# 05-GPS_IMU_SENSORS.net
KiCad netlist of a schematic drawn in Altium Designer
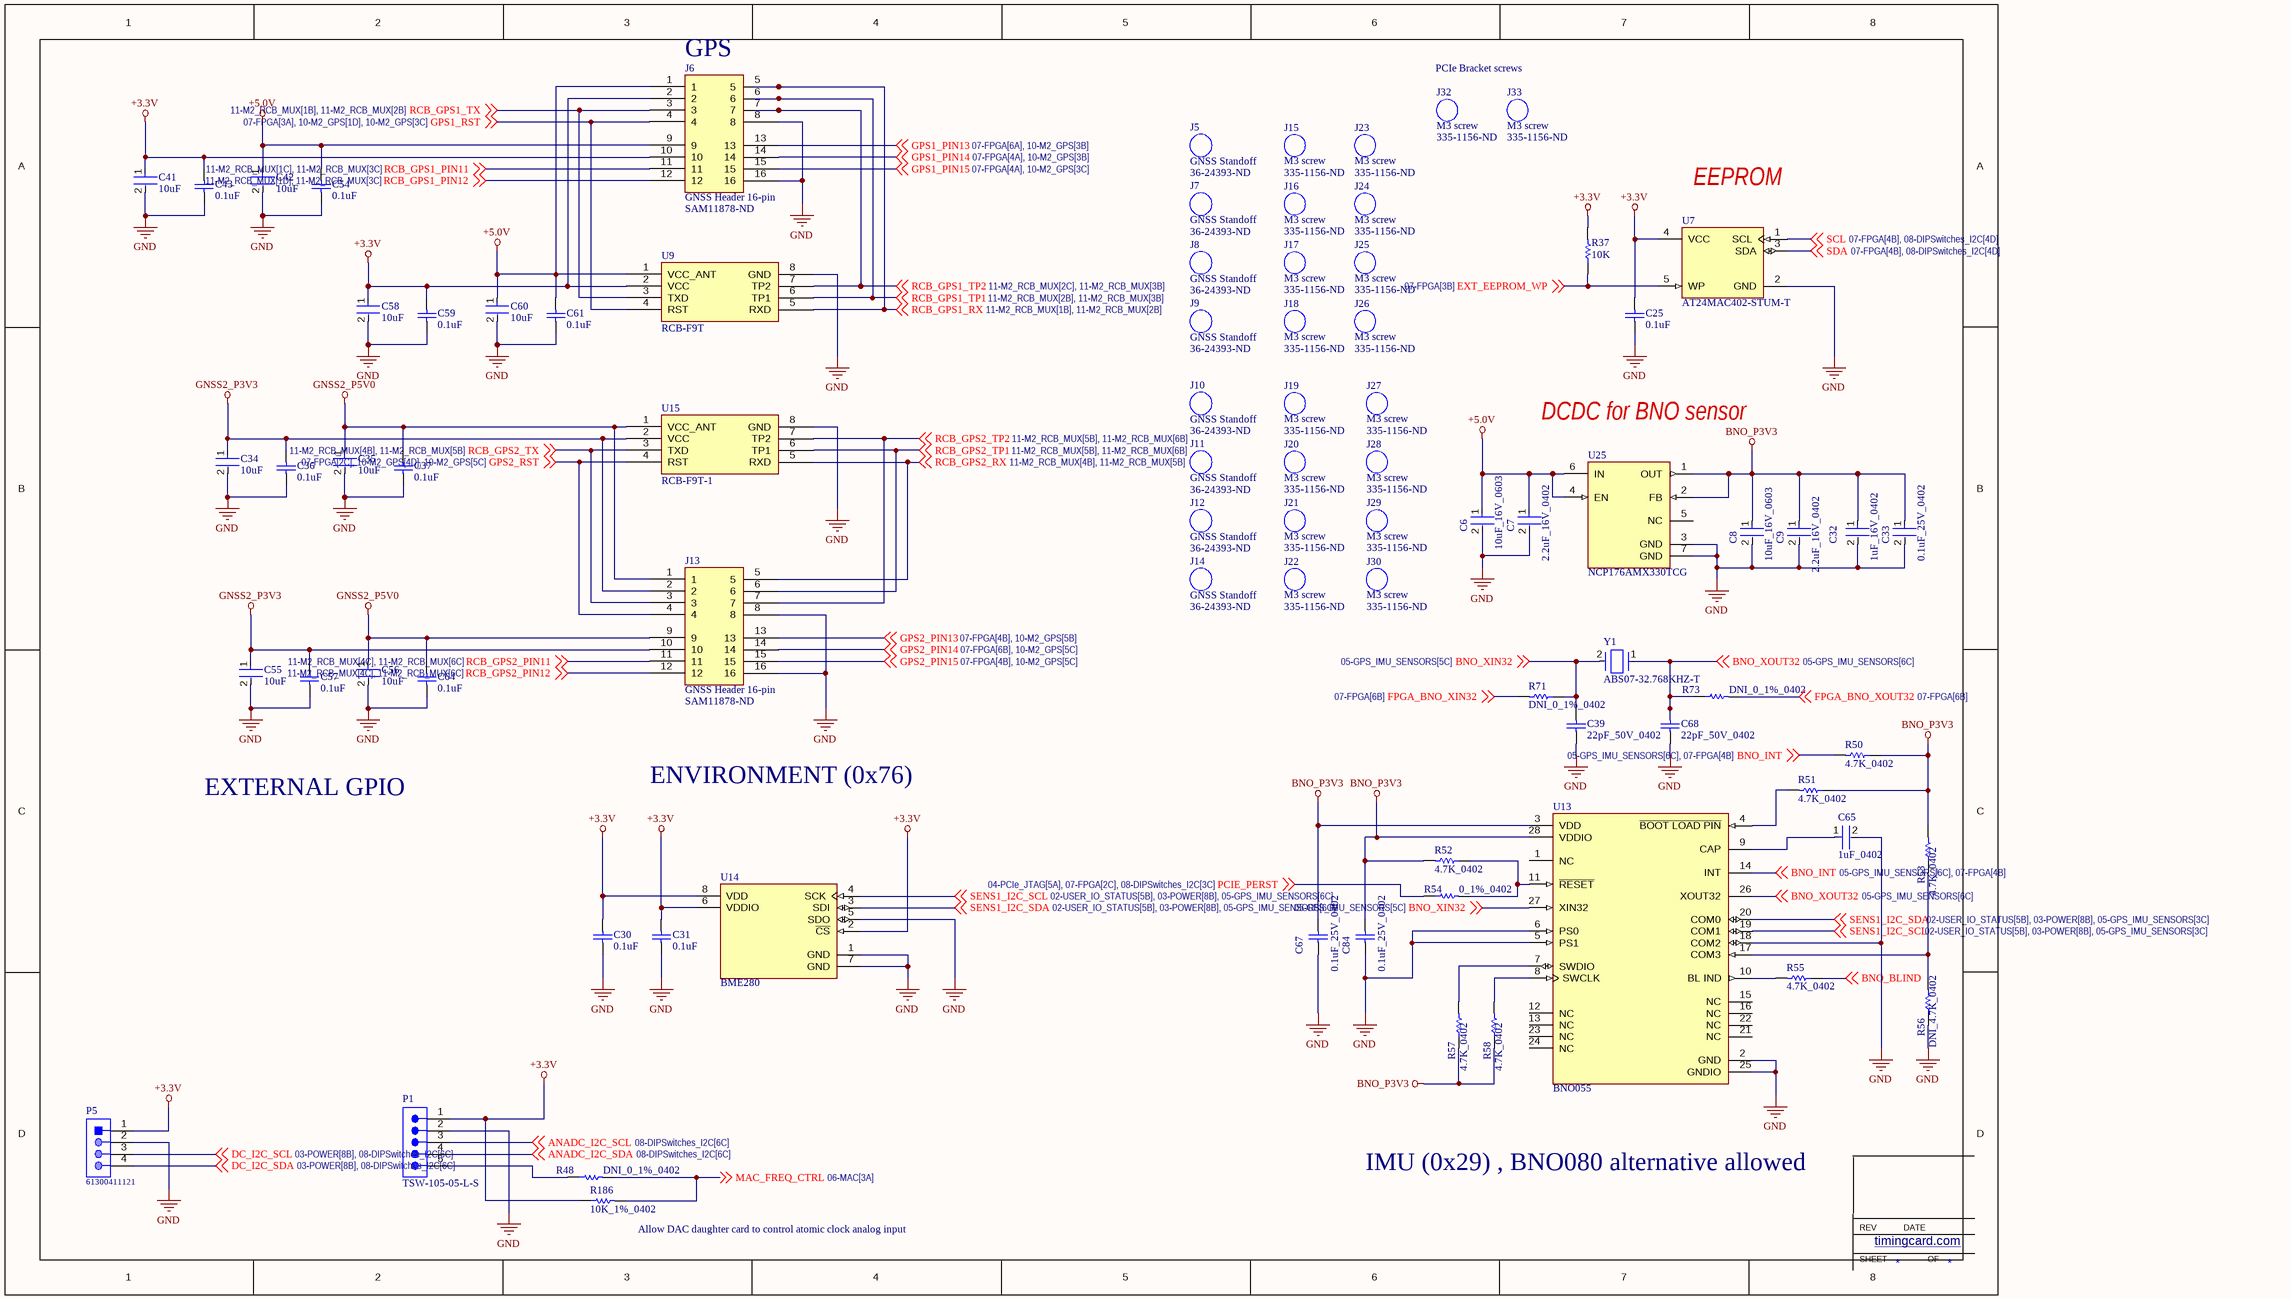
[diagram p0: 05-GPS_IMU_SENSORS.SchDoc]

(export (version "E")
  (design (tool "Eeschema 10.0.6"))
  (components
    (comp (ref "C6")
      (value "10uF_16V_0603")
      (footprint "FP-0603-L_1_6_0_2-W_0_8_0-MFG")
      (description "Multilayer Ceramic Capacitor 10uF 16V X5R 20% SMD 0603 T/R")
      (fields (field (name "TOLERANCE") "20%"))
      (libsource (lib "Altium Content Vault") (part "b4654b650e69147ec39a6b967a45e02"))
    )
    (comp (ref "C7")
      (value "2.2uF_16V_0402")
      (footprint "FP-C1005-050-0_05-IPC_A")
      (description "Multilayer Ceramic Capacitors 2.2μF ±10% 16V X5R SMD 0402")
      (fields (field (name "TOLERANCE") "10%"))
      (libsource (lib "Altium Content Vault") (part "b4654b650e69147ec39a6b967a45e02"))
    )
    (comp (ref "C8")
      (value "10uF_16V_0603")
      (footprint "FP-0603-L_1_6_0_2-W_0_8_0-MFG")
      (description "Multilayer Ceramic Capacitor 10uF 16V X5R 20% SMD 0603 T/R")
      (fields (field (name "TOLERANCE") "20%"))
      (libsource (lib "Altium Content Vault") (part "b4654b650e69147ec39a6b967a45e02"))
    )
    (comp (ref "C9")
      (value "2.2uF_16V_0402")
      (footprint "FP-C1005-050-0_05-IPC_A")
      (description "Multilayer Ceramic Capacitors 2.2μF ±10% 16V X5R SMD 0402")
      (fields (field (name "TOLERANCE") "10%"))
      (libsource (lib "Altium Content Vault") (part "b4654b650e69147ec39a6b967a45e02"))
    )
    (comp (ref "C25")
      (value "0.1uF")
      (footprint "CAPC1608X87X45ML20T05")
      (description "C0603X104K5RACAUTO")
      (fields (field (name "MANUFACTURER") "Kemet"))
      (libsource (lib "Altium Content Vault") (part "CAP"))
    )
    (comp (ref "C30")
      (value "0.1uF")
      (footprint "CAPC1608X87X45ML20T05")
      (description "C0603X104K5RACAUTO")
      (fields (field (name "MANUFACTURER") "Kemet"))
      (libsource (lib "Altium Content Vault") (part "CAP"))
    )
    (comp (ref "C31")
      (value "0.1uF")
      (footprint "CAPC1608X87X45ML20T05")
      (description "C0603X104K5RACAUTO")
      (fields (field (name "MANUFACTURER") "Kemet"))
      (libsource (lib "Altium Content Vault") (part "CAP"))
    )
    (comp (ref "C32")
      (value "1uF_16V_0402")
      (footprint "FP-0402-L_1_0_0_05-W_0_5-IPC_A")
      (description "None")
      (fields (field (name "TOLERANCE") "10%"))
      (libsource (lib "Altium Content Vault") (part "b4654b650e69147ec39a6b967a45e02"))
    )
    (comp (ref "C33")
      (value "0.1uF_25V_0402")
      (footprint "FP-0402-L_1_0_1-W_0_5_0_1-IPC_C")
      (description "General Purpose Ceramic Capacitor, 0402, 100nF, 10%, X7R, 15%, 25V")
      (fields (field (name "VOLTAGE") "25V") (field (name "TOLERANCE") "10%"))
      (libsource (lib "Altium Content Vault") (part "b4654b650e69147ec39a6b967a45e02"))
    )
    (comp (ref "C34")
      (value "10uF")
      (footprint "FP-MK212BG-MFG")
      (description "None")
      (fields (field (name "TOLERANCE") "10%") (field (name "VOLTAGE") "16V"))
      (libsource (lib "Altium Content Vault") (part "b4654b650e69147ec39a6b967a45e02"))
    )
    (comp (ref "C35")
      (value "10uF")
      (footprint "FP-MK212BG-MFG")
      (description "None")
      (fields (field (name "TOLERANCE") "10%") (field (name "VOLTAGE") "16V"))
      (libsource (lib "Altium Content Vault") (part "b4654b650e69147ec39a6b967a45e02"))
    )
    (comp (ref "C36")
      (value "0.1uF")
      (footprint "CAPC1608X87X45ML20T05")
      (description "C0603X104K5RACAUTO")
      (fields (field (name "MANUFACTURER") "Kemet"))
      (libsource (lib "Altium Content Vault") (part "CAP"))
    )
    (comp (ref "C37")
      (value "0.1uF")
      (footprint "CAPC1608X87X45ML20T05")
      (description "C0603X104K5RACAUTO")
      (fields (field (name "MANUFACTURER") "Kemet"))
      (libsource (lib "Altium Content Vault") (part "CAP"))
    )
    (comp (ref "C39")
      (value "22pF_50V_0402")
      (footprint "CAPC1005X55X25ML05T05")
      (description "Chip Capacitor, 22 pF, +/- 5%, 50 V, -55 to 125 degC, 0402 (1005 Metric), RoHS, Tape and Reel")
      (fields (field (name "MANUFACTURER") "Yageo") (field (name "TOLERANCE") "5%"))
      (libsource (lib "Altium Content Vault") (part "CAP-NP-2"))
    )
    (comp (ref "C41")
      (value "10uF")
      (footprint "FP-MK212BG-MFG")
      (description "None")
      (fields (field (name "TOLERANCE") "10%") (field (name "VOLTAGE") "16V"))
      (libsource (lib "Altium Content Vault") (part "b4654b650e69147ec39a6b967a45e02"))
    )
    (comp (ref "C42")
      (value "10uF")
      (footprint "FP-MK212BG-MFG")
      (description "None")
      (fields (field (name "TOLERANCE") "10%") (field (name "VOLTAGE") "16V"))
      (libsource (lib "Altium Content Vault") (part "b4654b650e69147ec39a6b967a45e02"))
    )
    (comp (ref "C43")
      (value "0.1uF")
      (footprint "CAPC1608X87X45ML20T05")
      (description "C0603X104K5RACAUTO")
      (fields (field (name "MANUFACTURER") "Kemet"))
      (libsource (lib "Altium Content Vault") (part "CAP"))
    )
    (comp (ref "C54")
      (value "0.1uF")
      (footprint "CAPC1608X87X45ML20T05")
      (description "C0603X104K5RACAUTO")
      (fields (field (name "MANUFACTURER") "Kemet"))
      (libsource (lib "Altium Content Vault") (part "CAP"))
    )
    (comp (ref "C55")
      (value "10uF")
      (footprint "FP-MK212BG-MFG")
      (description "None")
      (fields (field (name "TOLERANCE") "10%") (field (name "VOLTAGE") "16V"))
      (libsource (lib "Altium Content Vault") (part "b4654b650e69147ec39a6b967a45e02"))
    )
    (comp (ref "C56")
      (value "10uF")
      (footprint "FP-MK212BG-MFG")
      (description "None")
      (fields (field (name "TOLERANCE") "10%") (field (name "VOLTAGE") "16V"))
      (libsource (lib "Altium Content Vault") (part "b4654b650e69147ec39a6b967a45e02"))
    )
    (comp (ref "C57")
      (value "0.1uF")
      (footprint "CAPC1608X87X45ML20T05")
      (description "C0603X104K5RACAUTO")
      (fields (field (name "MANUFACTURER") "Kemet"))
      (libsource (lib "Altium Content Vault") (part "CAP"))
    )
    (comp (ref "C58")
      (value "10uF")
      (footprint "FP-MK212BG-MFG")
      (description "None")
      (fields (field (name "TOLERANCE") "10%") (field (name "VOLTAGE") "16V"))
      (libsource (lib "Altium Content Vault") (part "b4654b650e69147ec39a6b967a45e02"))
    )
    (comp (ref "C59")
      (value "0.1uF")
      (footprint "CAPC1608X87X45ML20T05")
      (description "C0603X104K5RACAUTO")
      (fields (field (name "MANUFACTURER") "Kemet"))
      (libsource (lib "Altium Content Vault") (part "CAP"))
    )
    (comp (ref "C60")
      (value "10uF")
      (footprint "FP-MK212BG-MFG")
      (description "None")
      (fields (field (name "TOLERANCE") "10%") (field (name "VOLTAGE") "16V"))
      (libsource (lib "Altium Content Vault") (part "b4654b650e69147ec39a6b967a45e02"))
    )
    (comp (ref "C61")
      (value "0.1uF")
      (footprint "CAPC1608X87X45ML20T05")
      (description "C0603X104K5RACAUTO")
      (fields (field (name "MANUFACTURER") "Kemet"))
      (libsource (lib "Altium Content Vault") (part "CAP"))
    )
    (comp (ref "C64")
      (value "0.1uF")
      (footprint "CAPC1608X87X45ML20T05")
      (description "C0603X104K5RACAUTO")
      (fields (field (name "MANUFACTURER") "Kemet"))
      (libsource (lib "Altium Content Vault") (part "CAP"))
    )
    (comp (ref "C65")
      (value "1uF_0402")
      (footprint "FP-0402-L_1_0_0_05-W_0_5-IPC_C")
      (description "None")
      (fields (field (name "TOLERANCE") "20%") (field (name "VOLTAGE") "16V"))
      (libsource (lib "Altium Content Vault") (part "b4654b650e69147ec39a6b967a45e02"))
    )
    (comp (ref "C67")
      (value "0.1uF_25V_0402")
      (footprint "CAPC1005X56X25NL10T15")
      (fields
        (field (name "PART NUMBER") "04023D104KAT2A")
        (field (name "MANUFACTURER") "AVX Interconnect / Elco")
      )
      (libsource (lib "Altium Content Vault") (part "CAP"))
    )
    (comp (ref "C68")
      (value "22pF_50V_0402")
      (footprint "CAPC1005X55X25ML05T05")
      (description "Chip Capacitor, 22 pF, +/- 5%, 50 V, -55 to 125 degC, 0402 (1005 Metric), RoHS, Tape and Reel")
      (fields (field (name "MANUFACTURER") "Yageo") (field (name "TOLERANCE") "5%"))
      (libsource (lib "Altium Content Vault") (part "CAP-NP-2"))
    )
    (comp (ref "C84")
      (value "0.1uF_25V_0402")
      (footprint "CAPC1005X56X25NL10T15")
      (fields
        (field (name "PART NUMBER") "04023D104KAT2A")
        (field (name "MANUFACTURER") "AVX Interconnect / Elco")
      )
      (libsource (lib "Altium Content Vault") (part "CAP"))
    )
    (comp (ref "J5")
      (value "GNSS Standoff")
      (fields (field (name "SUPPLIER PART NUMBER 1") "36-24393-ND"))
      (libsource (lib "FPGA_CONN") (part "GNSS Standoff"))
    )
    (comp (ref "J6")
      (value "GNSS Header 16-pin")
      (footprint "GNSS Header 16-pin")
      (fields (field (name "SUPPLIER PART NUMBER 1") "SAM11878-ND"))
      (libsource (lib "FPGA_CONN") (part "GNSS Header 16-pin"))
    )
    (comp (ref "J7")
      (value "GNSS Standoff")
      (fields (field (name "SUPPLIER PART NUMBER 1") "36-24393-ND"))
      (libsource (lib "FPGA_CONN") (part "GNSS Standoff"))
    )
    (comp (ref "J8")
      (value "GNSS Standoff")
      (fields (field (name "SUPPLIER PART NUMBER 1") "36-24393-ND"))
      (libsource (lib "FPGA_CONN") (part "GNSS Standoff"))
    )
    (comp (ref "J9")
      (value "GNSS Standoff")
      (fields (field (name "SUPPLIER PART NUMBER 1") "36-24393-ND"))
      (libsource (lib "FPGA_CONN") (part "GNSS Standoff"))
    )
    (comp (ref "J10")
      (value "GNSS Standoff")
      (fields (field (name "SUPPLIER PART NUMBER 1") "36-24393-ND"))
      (libsource (lib "FPGA_CONN") (part "GNSS Standoff"))
    )
    (comp (ref "J11")
      (value "GNSS Standoff")
      (fields (field (name "SUPPLIER PART NUMBER 1") "36-24393-ND"))
      (libsource (lib "FPGA_CONN") (part "GNSS Standoff"))
    )
    (comp (ref "J12")
      (value "GNSS Standoff")
      (fields (field (name "SUPPLIER PART NUMBER 1") "36-24393-ND"))
      (libsource (lib "FPGA_CONN") (part "GNSS Standoff"))
    )
    (comp (ref "J13")
      (value "GNSS Header 16-pin")
      (footprint "GNSS Header 16-pin")
      (fields (field (name "SUPPLIER PART NUMBER 1") "SAM11878-ND"))
      (libsource (lib "FPGA_CONN") (part "GNSS Header 16-pin"))
    )
    (comp (ref "J14")
      (value "GNSS Standoff")
      (fields (field (name "SUPPLIER PART NUMBER 1") "36-24393-ND"))
      (libsource (lib "FPGA_CONN") (part "GNSS Standoff"))
    )
    (comp (ref "J15")
      (value "M3 screw")
      (fields (field (name "SUPPLIER PART NUMBER 1") "335-1156-ND"))
      (libsource (lib "FPGA_CONN") (part "M3 screw"))
    )
    (comp (ref "J16")
      (value "M3 screw")
      (fields (field (name "SUPPLIER PART NUMBER 1") "335-1156-ND"))
      (libsource (lib "FPGA_CONN") (part "M3 screw"))
    )
    (comp (ref "J17")
      (value "M3 screw")
      (fields (field (name "SUPPLIER PART NUMBER 1") "335-1156-ND"))
      (libsource (lib "FPGA_CONN") (part "M3 screw"))
    )
    (comp (ref "J18")
      (value "M3 screw")
      (fields (field (name "SUPPLIER PART NUMBER 1") "335-1156-ND"))
      (libsource (lib "FPGA_CONN") (part "M3 screw"))
    )
    (comp (ref "J19")
      (value "M3 screw")
      (fields (field (name "SUPPLIER PART NUMBER 1") "335-1156-ND"))
      (libsource (lib "FPGA_CONN") (part "M3 screw"))
    )
    (comp (ref "J20")
      (value "M3 screw")
      (fields (field (name "SUPPLIER PART NUMBER 1") "335-1156-ND"))
      (libsource (lib "FPGA_CONN") (part "M3 screw"))
    )
    (comp (ref "J21")
      (value "M3 screw")
      (fields (field (name "SUPPLIER PART NUMBER 1") "335-1156-ND"))
      (libsource (lib "FPGA_CONN") (part "M3 screw"))
    )
    (comp (ref "J22")
      (value "M3 screw")
      (fields (field (name "SUPPLIER PART NUMBER 1") "335-1156-ND"))
      (libsource (lib "FPGA_CONN") (part "M3 screw"))
    )
    (comp (ref "J23")
      (value "M3 screw")
      (fields (field (name "SUPPLIER PART NUMBER 1") "335-1156-ND"))
      (libsource (lib "FPGA_CONN") (part "M3 screw"))
    )
    (comp (ref "J24")
      (value "M3 screw")
      (fields (field (name "SUPPLIER PART NUMBER 1") "335-1156-ND"))
      (libsource (lib "FPGA_CONN") (part "M3 screw"))
    )
    (comp (ref "J25")
      (value "M3 screw")
      (fields (field (name "SUPPLIER PART NUMBER 1") "335-1156-ND"))
      (libsource (lib "FPGA_CONN") (part "M3 screw"))
    )
    (comp (ref "J26")
      (value "M3 screw")
      (fields (field (name "SUPPLIER PART NUMBER 1") "335-1156-ND"))
      (libsource (lib "FPGA_CONN") (part "M3 screw"))
    )
    (comp (ref "J27")
      (value "M3 screw")
      (fields (field (name "SUPPLIER PART NUMBER 1") "335-1156-ND"))
      (libsource (lib "FPGA_CONN") (part "M3 screw"))
    )
    (comp (ref "J28")
      (value "M3 screw")
      (fields (field (name "SUPPLIER PART NUMBER 1") "335-1156-ND"))
      (libsource (lib "FPGA_CONN") (part "M3 screw"))
    )
    (comp (ref "J29")
      (value "M3 screw")
      (fields (field (name "SUPPLIER PART NUMBER 1") "335-1156-ND"))
      (libsource (lib "FPGA_CONN") (part "M3 screw"))
    )
    (comp (ref "J30")
      (value "M3 screw")
      (fields (field (name "SUPPLIER PART NUMBER 1") "335-1156-ND"))
      (libsource (lib "FPGA_CONN") (part "M3 screw"))
    )
    (comp (ref "J32")
      (value "M3 screw")
      (fields (field (name "SUPPLIER PART NUMBER 1") "335-1156-ND"))
      (libsource (lib "FPGA_CONN") (part "M3 screw"))
    )
    (comp (ref "J33")
      (value "M3 screw")
      (fields (field (name "SUPPLIER PART NUMBER 1") "335-1156-ND"))
      (libsource (lib "FPGA_CONN") (part "M3 screw"))
    )
    (comp (ref "P1")
      (value "TSW-105-05-L-S")
      (footprint "SMTC-TSW-105-05-X-S")
      (description "0.025\" SQ Post Header, Through-hole, Vertical, -55 to 125 degC, 2.54 mm Pitch, 5-Pin, Male, RoHS")
      (fields (field (name "MANUFACTURER") "Samtec"))
      (libsource (lib "Altium Content Vault") (part "SMTC-TSW-105-05-X-S"))
    )
    (comp (ref "P5")
      (value "61300411121")
      (footprint "61300411121")
      (description "THT Vertical Pin Header WR-PHD, Pitch 2.54 mm, Single Row, 4 pins")
      (fields (field (name "MANUFACTURER") "Wurth Elektronik") (field (name "PUBLISHER") "WurthElektronik"))
      (libsource (lib "Altium Content Vault") (part "WE-CN-1P-M-R4"))
    )
    (comp (ref "R37")
      (value "10K")
      (footprint "RESC1608X55X30LL15T20")
      (fields (field (name "TOLERANCE") "±1%") (field (name "MANUFACTURER") "Stackpole-Electronics-Inc."))
      (libsource (lib "Altium Content Vault") (part "RES-2"))
    )
    (comp (ref "R48")
      (value "DNI_0_1%_0402")
      (footprint "RESC1005X40X25LL05T05")
      (description "Chip Resistor, 0 Ohm, 0.1 W, -55 to 155 degC, 0402 (1005 Metric), RoHS, Tape and Reel")
      (fields (field (name "MANUFACTURER") "Panasonic") (field (name "TOLERANCE") "5%"))
      (libsource (lib "Altium Content Vault") (part "RES-2"))
    )
    (comp (ref "R50")
      (value "4.7K_0402")
      (footprint "RESC1005X40X25LL05T05")
      (description "Chip Resistor, 4.7 KOhm, +/- 1%, 0.1 W, -55 to 155 degC, 0402 (1005 Metric), RoHS, Tape and Reel")
      (fields (field (name "TOLERANCE") "1%") (field (name "PARTNUMBER") "ERJ-2RKF4701X"))
      (libsource (lib "Altium Content Vault") (part "RES-2"))
    )
    (comp (ref "R51")
      (value "4.7K_0402")
      (footprint "RESC1005X40X25LL05T05")
      (description "Chip Resistor, 4.7 KOhm, +/- 1%, 0.1 W, -55 to 155 degC, 0402 (1005 Metric), RoHS, Tape and Reel")
      (fields (field (name "TOLERANCE") "1%") (field (name "PARTNUMBER") "ERJ-2RKF4701X"))
      (libsource (lib "Altium Content Vault") (part "RES-2"))
    )
    (comp (ref "R52")
      (value "4.7K_0402")
      (footprint "RESC1005X40X25LL05T05")
      (description "Chip Resistor, 4.7 KOhm, +/- 1%, 0.1 W, -55 to 155 degC, 0402 (1005 Metric), RoHS, Tape and Reel")
      (fields (field (name "TOLERANCE") "1%") (field (name "PARTNUMBER") "ERJ-2RKF4701X"))
      (libsource (lib "Altium Content Vault") (part "RES-2"))
    )
    (comp (ref "R53")
      (value "4.7K_0402")
      (footprint "RESC1005X40X25LL05T05")
      (description "Chip Resistor, 4.7 KOhm, +/- 1%, 0.1 W, -55 to 155 degC, 0402 (1005 Metric), RoHS, Tape and Reel")
      (fields (field (name "TOLERANCE") "1%") (field (name "PARTNUMBER") "ERJ-2RKF4701X"))
      (libsource (lib "Altium Content Vault") (part "RES-2"))
    )
    (comp (ref "R54")
      (value "0_1%_0402")
      (footprint "RESC1005X40X25LL05T05")
      (description "Chip Resistor, 0 Ohm, 0.1 W, -55 to 155 degC, 0402 (1005 Metric), RoHS, Tape and Reel")
      (fields (field (name "MANUFACTURER") "Panasonic") (field (name "TOLERANCE") "5%"))
      (libsource (lib "Altium Content Vault") (part "RES-2"))
    )
    (comp (ref "R55")
      (value "4.7K_0402")
      (footprint "RESC1005X40X25LL05T05")
      (description "Chip Resistor, 4.7 KOhm, +/- 1%, 0.1 W, -55 to 155 degC, 0402 (1005 Metric), RoHS, Tape and Reel")
      (fields (field (name "TOLERANCE") "1%") (field (name "PARTNUMBER") "ERJ-2RKF4701X"))
      (libsource (lib "Altium Content Vault") (part "RES-2"))
    )
    (comp (ref "R56")
      (value "DNI_4.7K_0402")
      (footprint "RESC1005X40X25LL05T05")
      (description "Chip Resistor, 4.7 KOhm, +/- 1%, 0.1 W, -55 to 155 degC, 0402 (1005 Metric), RoHS, Tape and Reel")
      (fields (field (name "TOLERANCE") "1%") (field (name "PARTNUMBER") "ERJ-2RKF4701X"))
      (libsource (lib "Altium Content Vault") (part "RES-2"))
    )
    (comp (ref "R57")
      (value "4.7K_0402")
      (footprint "RESC1005X40X25LL05T05")
      (description "Chip Resistor, 4.7 KOhm, +/- 1%, 0.1 W, -55 to 155 degC, 0402 (1005 Metric), RoHS, Tape and Reel")
      (fields (field (name "TOLERANCE") "1%") (field (name "PARTNUMBER") "ERJ-2RKF4701X"))
      (libsource (lib "Altium Content Vault") (part "RES-2"))
    )
    (comp (ref "R58")
      (value "4.7K_0402")
      (footprint "RESC1005X40X25LL05T05")
      (description "Chip Resistor, 4.7 KOhm, +/- 1%, 0.1 W, -55 to 155 degC, 0402 (1005 Metric), RoHS, Tape and Reel")
      (fields (field (name "TOLERANCE") "1%") (field (name "PARTNUMBER") "ERJ-2RKF4701X"))
      (libsource (lib "Altium Content Vault") (part "RES-2"))
    )
    (comp (ref "R71")
      (value "DNI_0_1%_0402")
      (footprint "RESC1005X40X25LL05T05")
      (description "Chip Resistor, 0 Ohm, 0.1 W, -55 to 155 degC, 0402 (1005 Metric), RoHS, Tape and Reel")
      (fields (field (name "MANUFACTURER") "Panasonic") (field (name "TOLERANCE") "5%"))
      (libsource (lib "Altium Content Vault") (part "RES-2"))
    )
    (comp (ref "R73")
      (value "DNI_0_1%_0402")
      (footprint "RESC1005X40X25LL05T05")
      (description "Chip Resistor, 0 Ohm, 0.1 W, -55 to 155 degC, 0402 (1005 Metric), RoHS, Tape and Reel")
      (fields (field (name "MANUFACTURER") "Panasonic") (field (name "TOLERANCE") "5%"))
      (libsource (lib "Altium Content Vault") (part "RES-2"))
    )
    (comp (ref "R186")
      (value "10K_1%_0402")
      (footprint "RESC1005X40X25LL05T10")
      (fields (field (name "PART NUMBER") "RC0402FR-0710KL") (field (name "MANUFACTURER") "Yageo / Phycomp"))
      (libsource (lib "Altium Content Vault") (part "RES"))
    )
    (comp (ref "U7")
      (value "AT24MAC402-STUM-T")
      (footprint "FP-5TS1-IPC_C")
      (description "IC EEPROM 2K I2C 1MHZ SOT23-5")
      (fields
        (field (name "MANUFACTURER") "Microchip")
        (field (name "OCTOPART") "https://octopart.com/at24mac402-stum-t-microchip-77758112")
      )
      (libsource (lib "Altium Content Vault") (part "93fe34f5f049140596bab6421a6454b"))
    )
    (comp (ref "U9")
      (value "RCB-F9T")
      (footprint "GNSS")
      (description "MOD, GPS")
      (fields (field (name "VELENTIUM PART NUM") "<V PART NUM>"))
      (libsource (lib "Modules") (part "RCB-F9T"))
    )
    (comp (ref "U13")
      (value "BNO055")
      (footprint "FP-BNO055-MFG")
      (description "IMU ACCEL/GYRO/MAG I2C 28LGA")
      (libsource (lib "Altium Content Vault") (part "ba837af00a0b6167256f888b31462b1"))
    )
    (comp (ref "U14")
      (value "BME280")
      (footprint "FP-BME280-MFG")
      (description "SENSOR PRESSURE HUMIDITY TEMP")
      (libsource (lib "Altium Content Vault") (part "d58e2f6669bc67e6a2bc6a28610ca79"))
    )
    (comp (ref "U15")
      (value "RCB-F9T-1")
      (footprint "GNSS")
      (description "MOD, GPS")
      (fields (field (name "VELENTIUM PART NUM") "<V PART NUM>"))
      (libsource (lib "Modules") (part "RCB-F9T"))
    )
    (comp (ref "U25")
      (value "NCP176AMX330TCG")
      (footprint "FP-711AT-MFG")
      (description "IC REG LINEAR 3.3V 500MA 6XDFN")
      (fields
        (field (name "MANUFACTURER") "ON Semiconductor")
        (field (name "OCTOPART") "https://octopart.com/ncp176amx330tcg-on+semiconductor-61522616")
      )
      (libsource (lib "Altium Content Vault") (part "a38d0f79c2a9f01c07a7e52882ed186"))
    )
    (comp (ref "Y1")
      (value "ABS07-32.768KHZ-T")
      (footprint "FP-ABS07-MFG")
      (description "Crystal 32.768kHz ±20ppm (Tol) 12.5pF FUND 70kΩ 2-Pin CSMD T/R")
      (fields (field (name "TOLERANCE") "20ppm"))
      (libsource (lib "Altium Content Vault") (part "c23a69dc6c9e2f18f2079038eb95dd1"))
    )
  )
  (nets
    (net (code "1") (name "+3.3V") (class "Default")
      (node (ref "C25") (pin "2") (pinfunction "2_2") (pintype "passive"))
      (node (ref "C30") (pin "2") (pinfunction "2_2") (pintype "passive"))
      (node (ref "C31") (pin "2") (pinfunction "2_2") (pintype "passive"))
      (node (ref "C41") (pin "1") (pinfunction "1_1") (pintype "passive"))
      (node (ref "C43") (pin "2") (pinfunction "2_2") (pintype "passive"))
      (node (ref "C58") (pin "1") (pinfunction "1_1") (pintype "passive"))
      (node (ref "C59") (pin "2") (pinfunction "2_2") (pintype "passive"))
      (node (ref "J6") (pin "10") (pinfunction "10_10") (pintype "passive"))
      (node (ref "J6") (pin "2") (pinfunction "2_2") (pintype "passive"))
      (node (ref "P1") (pin "1") (pinfunction "1_1") (pintype "passive"))
      (node (ref "P5") (pin "1") (pinfunction "1_1") (pintype "passive"))
      (node (ref "R186") (pin "1") (pinfunction "1_1") (pintype "passive"))
      (node (ref "R37") (pin "2") (pinfunction "2_2") (pintype "passive"))
      (node (ref "U14") (pin "2") (pinfunction "~{CS}_2") (pintype "input"))
      (node (ref "U14") (pin "6") (pinfunction "VDDIO_6") (pintype "power_in"))
      (node (ref "U14") (pin "8") (pinfunction "VDD_8") (pintype "power_in"))
      (node (ref "U7") (pin "4") (pinfunction "VCC_4") (pintype "power_in"))
      (node (ref "U9") (pin "2") (pinfunction "VCC_2") (pintype "passive"))
    )
    (net (code "2") (name "+5.0V") (class "Default")
      (node (ref "C42") (pin "1") (pinfunction "1_1") (pintype "passive"))
      (node (ref "C54") (pin "2") (pinfunction "2_2") (pintype "passive"))
      (node (ref "C6") (pin "1") (pinfunction "1_1") (pintype "passive"))
      (node (ref "C60") (pin "1") (pinfunction "1_1") (pintype "passive"))
      (node (ref "C61") (pin "2") (pinfunction "2_2") (pintype "passive"))
      (node (ref "C7") (pin "1") (pinfunction "1_1") (pintype "passive"))
      (node (ref "J6") (pin "1") (pinfunction "1_1") (pintype "passive"))
      (node (ref "J6") (pin "9") (pinfunction "9_9") (pintype "passive"))
      (node (ref "U25") (pin "4") (pinfunction "EN_4") (pintype "input"))
      (node (ref "U25") (pin "6") (pinfunction "IN_6") (pintype "power_in"))
      (node (ref "U9") (pin "1") (pinfunction "VCC_ANT_1") (pintype "passive"))
    )
    (net (code "3") (name "ANADC_I2C_SCL") (class "Default")
      (node (ref "P1") (pin "3") (pinfunction "3_3") (pintype "passive"))
    )
    (net (code "4") (name "ANADC_I2C_SDA") (class "Default")
      (node (ref "P1") (pin "4") (pinfunction "4_4") (pintype "passive"))
    )
    (net (code "5") (name "BNO_BLIND") (class "Default")
      (node (ref "R55") (pin "1") (pinfunction "1_1") (pintype "passive"))
    )
    (net (code "6") (name "BNO_INT") (class "Default")
      (node (ref "R50") (pin "2") (pinfunction "2_2") (pintype "passive"))
      (node (ref "U13") (pin "14") (pinfunction "INT_14") (pintype "passive"))
    )
    (net (code "7") (name "BNO_P3V3") (class "Default")
      (node (ref "C32") (pin "1") (pinfunction "1_1") (pintype "passive"))
      (node (ref "C33") (pin "1") (pinfunction "1_1") (pintype "passive"))
      (node (ref "C67") (pin "2") (pinfunction "2_2") (pintype "passive"))
      (node (ref "C8") (pin "1") (pinfunction "1_1") (pintype "passive"))
      (node (ref "C84") (pin "2") (pinfunction "2_2") (pintype "passive"))
      (node (ref "C9") (pin "1") (pinfunction "1_1") (pintype "passive"))
      (node (ref "R50") (pin "1") (pinfunction "1_1") (pintype "passive"))
      (node (ref "R51") (pin "1") (pinfunction "1_1") (pintype "passive"))
      (node (ref "R52") (pin "2") (pinfunction "2_2") (pintype "passive"))
      (node (ref "R53") (pin "2") (pinfunction "2_2") (pintype "passive"))
      (node (ref "R57") (pin "1") (pinfunction "1_1") (pintype "passive"))
      (node (ref "R58") (pin "1") (pinfunction "1_1") (pintype "passive"))
      (node (ref "U13") (pin "28") (pinfunction "VDDIO_28") (pintype "power_in"))
      (node (ref "U13") (pin "3") (pinfunction "VDD_3") (pintype "power_in"))
      (node (ref "U25") (pin "1") (pinfunction "OUT_1") (pintype "output"))
      (node (ref "U25") (pin "2") (pinfunction "FB_2") (pintype "input"))
    )
    (net (code "8") (name "BNO_XIN32") (class "Default")
      (node (ref "C39") (pin "2") (pinfunction "2_2") (pintype "passive"))
      (node (ref "R71") (pin "1") (pinfunction "1_1") (pintype "passive"))
      (node (ref "U13") (pin "27") (pinfunction "XIN32_27") (pintype "input"))
      (node (ref "Y1") (pin "2") (pinfunction "2_2") (pintype "passive"))
    )
    (net (code "9") (name "BNO_XOUT32") (class "Default")
      (node (ref "C68") (pin "2") (pinfunction "2_2") (pintype "passive"))
      (node (ref "R73") (pin "1") (pinfunction "1_1") (pintype "passive"))
      (node (ref "U13") (pin "26") (pinfunction "XOUT32_26") (pintype "passive"))
      (node (ref "Y1") (pin "1") (pinfunction "1_1") (pintype "passive"))
    )
    (net (code "10") (name "DC_I2C_SCL") (class "Default")
      (node (ref "P5") (pin "3") (pinfunction "3_3") (pintype "passive"))
    )
    (net (code "11") (name "DC_I2C_SDA") (class "Default")
      (node (ref "P5") (pin "4") (pinfunction "4_4") (pintype "passive"))
    )
    (net (code "12") (name "EXT_EEPROM_WP") (class "Default")
      (node (ref "R37") (pin "1") (pinfunction "1_1") (pintype "passive"))
      (node (ref "U7") (pin "5") (pinfunction "WP_5") (pintype "input"))
    )
    (net (code "13") (name "FPGA_BNO_XIN32") (class "Default")
      (node (ref "R71") (pin "2") (pinfunction "2_2") (pintype "passive"))
    )
    (net (code "14") (name "FPGA_BNO_XOUT32") (class "Default")
      (node (ref "R73") (pin "2") (pinfunction "2_2") (pintype "passive"))
    )
    (net (code "15") (name "GND") (class "Default")
      (node (ref "C25") (pin "1") (pinfunction "1_1") (pintype "passive"))
      (node (ref "C30") (pin "1") (pinfunction "1_1") (pintype "passive"))
      (node (ref "C31") (pin "1") (pinfunction "1_1") (pintype "passive"))
      (node (ref "C32") (pin "2") (pinfunction "2_2") (pintype "passive"))
      (node (ref "C33") (pin "2") (pinfunction "2_2") (pintype "passive"))
      (node (ref "C34") (pin "2") (pinfunction "2_2") (pintype "passive"))
      (node (ref "C35") (pin "2") (pinfunction "2_2") (pintype "passive"))
      (node (ref "C36") (pin "1") (pinfunction "1_1") (pintype "passive"))
      (node (ref "C37") (pin "1") (pinfunction "1_1") (pintype "passive"))
      (node (ref "C39") (pin "1") (pinfunction "1_1") (pintype "passive"))
      (node (ref "C41") (pin "2") (pinfunction "2_2") (pintype "passive"))
      (node (ref "C42") (pin "2") (pinfunction "2_2") (pintype "passive"))
      (node (ref "C43") (pin "1") (pinfunction "1_1") (pintype "passive"))
      (node (ref "C54") (pin "1") (pinfunction "1_1") (pintype "passive"))
      (node (ref "C55") (pin "2") (pinfunction "2_2") (pintype "passive"))
      (node (ref "C56") (pin "2") (pinfunction "2_2") (pintype "passive"))
      (node (ref "C57") (pin "1") (pinfunction "1_1") (pintype "passive"))
      (node (ref "C58") (pin "2") (pinfunction "2_2") (pintype "passive"))
      (node (ref "C59") (pin "1") (pinfunction "1_1") (pintype "passive"))
      (node (ref "C6") (pin "2") (pinfunction "2_2") (pintype "passive"))
      (node (ref "C60") (pin "2") (pinfunction "2_2") (pintype "passive"))
      (node (ref "C61") (pin "1") (pinfunction "1_1") (pintype "passive"))
      (node (ref "C64") (pin "1") (pinfunction "1_1") (pintype "passive"))
      (node (ref "C65") (pin "2") (pinfunction "2_2") (pintype "passive"))
      (node (ref "C67") (pin "1") (pinfunction "1_1") (pintype "passive"))
      (node (ref "C68") (pin "1") (pinfunction "1_1") (pintype "passive"))
      (node (ref "C7") (pin "2") (pinfunction "2_2") (pintype "passive"))
      (node (ref "C8") (pin "2") (pinfunction "2_2") (pintype "passive"))
      (node (ref "C84") (pin "1") (pinfunction "1_1") (pintype "passive"))
      (node (ref "C9") (pin "2") (pinfunction "2_2") (pintype "passive"))
      (node (ref "J13") (pin "16") (pinfunction "16_16") (pintype "passive"))
      (node (ref "J13") (pin "8") (pinfunction "8_8") (pintype "passive"))
      (node (ref "J6") (pin "16") (pinfunction "16_16") (pintype "passive"))
      (node (ref "J6") (pin "8") (pinfunction "8_8") (pintype "passive"))
      (node (ref "P1") (pin "2") (pinfunction "2_2") (pintype "passive"))
      (node (ref "P5") (pin "2") (pinfunction "2_2") (pintype "passive"))
      (node (ref "R56") (pin "1") (pinfunction "1_1") (pintype "passive"))
      (node (ref "U13") (pin "18") (pinfunction "COM2_18") (pintype "bidirectional"))
      (node (ref "U13") (pin "2") (pinfunction "GND_2") (pintype "power_in"))
      (node (ref "U13") (pin "25") (pinfunction "GNDIO_25") (pintype "power_in"))
      (node (ref "U13") (pin "5") (pinfunction "PS1_5") (pintype "input"))
      (node (ref "U13") (pin "6") (pinfunction "PS0_6") (pintype "input"))
      (node (ref "U14") (pin "1") (pinfunction "GND_1") (pintype "power_in"))
      (node (ref "U14") (pin "5") (pinfunction "SDO_5") (pintype "bidirectional"))
      (node (ref "U14") (pin "7") (pinfunction "GND_7") (pintype "power_in"))
      (node (ref "U15") (pin "8") (pinfunction "GND_8") (pintype "passive"))
      (node (ref "U25") (pin "3") (pinfunction "GND_3") (pintype "power_in"))
      (node (ref "U25") (pin "7") (pinfunction "GND_7") (pintype "power_in"))
      (node (ref "U7") (pin "2") (pinfunction "GND_2") (pintype "power_in"))
      (node (ref "U9") (pin "8") (pinfunction "GND_8") (pintype "passive"))
    )
    (net (code "16") (name "GNSS2_P3V3") (class "Default")
      (node (ref "C34") (pin "1") (pinfunction "1_1") (pintype "passive"))
      (node (ref "C36") (pin "2") (pinfunction "2_2") (pintype "passive"))
      (node (ref "C55") (pin "1") (pinfunction "1_1") (pintype "passive"))
      (node (ref "C57") (pin "2") (pinfunction "2_2") (pintype "passive"))
      (node (ref "J13") (pin "10") (pinfunction "10_10") (pintype "passive"))
      (node (ref "J13") (pin "2") (pinfunction "2_2") (pintype "passive"))
      (node (ref "U15") (pin "2") (pinfunction "VCC_2") (pintype "passive"))
    )
    (net (code "17") (name "GNSS2_P5V0") (class "Default")
      (node (ref "C35") (pin "1") (pinfunction "1_1") (pintype "passive"))
      (node (ref "C37") (pin "2") (pinfunction "2_2") (pintype "passive"))
      (node (ref "C56") (pin "1") (pinfunction "1_1") (pintype "passive"))
      (node (ref "C64") (pin "2") (pinfunction "2_2") (pintype "passive"))
      (node (ref "J13") (pin "1") (pinfunction "1_1") (pintype "passive"))
      (node (ref "J13") (pin "9") (pinfunction "9_9") (pintype "passive"))
      (node (ref "U15") (pin "1") (pinfunction "VCC_ANT_1") (pintype "passive"))
    )
    (net (code "18") (name "GPS1_PIN13") (class "Default")
      (node (ref "J6") (pin "13") (pinfunction "13_13") (pintype "passive"))
    )
    (net (code "19") (name "GPS1_PIN14") (class "Default")
      (node (ref "J6") (pin "14") (pinfunction "14_14") (pintype "passive"))
    )
    (net (code "20") (name "GPS1_PIN15") (class "Default")
      (node (ref "J6") (pin "15") (pinfunction "15_15") (pintype "passive"))
    )
    (net (code "21") (name "GPS1_RST") (class "Default")
      (node (ref "J6") (pin "4") (pinfunction "4_4") (pintype "passive"))
      (node (ref "U9") (pin "4") (pinfunction "RST_4") (pintype "passive"))
    )
    (net (code "22") (name "GPS2_PIN13") (class "Default")
      (node (ref "J13") (pin "13") (pinfunction "13_13") (pintype "passive"))
    )
    (net (code "23") (name "GPS2_PIN14") (class "Default")
      (node (ref "J13") (pin "14") (pinfunction "14_14") (pintype "passive"))
    )
    (net (code "24") (name "GPS2_PIN15") (class "Default")
      (node (ref "J13") (pin "15") (pinfunction "15_15") (pintype "passive"))
    )
    (net (code "25") (name "GPS2_RST") (class "Default")
      (node (ref "J13") (pin "4") (pinfunction "4_4") (pintype "passive"))
      (node (ref "U15") (pin "4") (pinfunction "RST_4") (pintype "passive"))
    )
    (net (code "26") (name "MAC_FREQ_CTRL") (class "Default")
      (node (ref "R186") (pin "2") (pinfunction "2_2") (pintype "passive"))
      (node (ref "R48") (pin "2") (pinfunction "2_2") (pintype "passive"))
    )
    (net (code "27") (name "Net-(P1-Pad5)") (class "Default")
      (node (ref "P1") (pin "5") (pinfunction "5_5") (pintype "passive"))
      (node (ref "R48") (pin "1") (pinfunction "1_1") (pintype "passive"))
    )
    (net (code "28") (name "Net-(U13-BL_IND)") (class "Default")
      (node (ref "R55") (pin "2") (pinfunction "2_2") (pintype "passive"))
      (node (ref "U13") (pin "10") (pinfunction "BL_IND_10") (pintype "output"))
    )
    (net (code "29") (name "Net-(U13-CAP)") (class "Default")
      (node (ref "C65") (pin "1") (pinfunction "1_1") (pintype "passive"))
      (node (ref "U13") (pin "9") (pinfunction "CAP_9") (pintype "passive"))
    )
    (net (code "30") (name "Net-(U13-COM3)") (class "Default")
      (node (ref "R53") (pin "1") (pinfunction "1_1") (pintype "passive"))
      (node (ref "R56") (pin "2") (pinfunction "2_2") (pintype "passive"))
      (node (ref "U13") (pin "17") (pinfunction "COM3_17") (pintype "input"))
    )
    (net (code "31") (name "Net-(U13-SWCLK)") (class "Default")
      (node (ref "R58") (pin "2") (pinfunction "2_2") (pintype "passive"))
      (node (ref "U13") (pin "8") (pinfunction "SWCLK_8") (pintype "input"))
    )
    (net (code "32") (name "Net-(U13-SWDIO)") (class "Default")
      (node (ref "R57") (pin "2") (pinfunction "2_2") (pintype "passive"))
      (node (ref "U13") (pin "7") (pinfunction "SWDIO_7") (pintype "bidirectional"))
    )
    (net (code "33") (name "Net-(U13-~{BOOT_LOAD_PIN})") (class "Default")
      (node (ref "R51") (pin "2") (pinfunction "2_2") (pintype "passive"))
      (node (ref "U13") (pin "4") (pinfunction "~{BOOT_LOAD_PIN}_4") (pintype "input"))
    )
    (net (code "34") (name "Net-(U13-~{RESET})") (class "Default")
      (node (ref "R52") (pin "1") (pinfunction "1_1") (pintype "passive"))
      (node (ref "R54") (pin "2") (pinfunction "2_2") (pintype "passive"))
      (node (ref "U13") (pin "11") (pinfunction "~{RESET}_11") (pintype "input"))
    )
    (net (code "35") (name "PCIE_PERST") (class "Default")
      (node (ref "R54") (pin "1") (pinfunction "1_1") (pintype "passive"))
    )
    (net (code "36") (name "RCB_GPS1_PIN11") (class "Default")
      (node (ref "J6") (pin "11") (pinfunction "11_11") (pintype "passive"))
    )
    (net (code "37") (name "RCB_GPS1_PIN12") (class "Default")
      (node (ref "J6") (pin "12") (pinfunction "12_12") (pintype "passive"))
    )
    (net (code "38") (name "RCB_GPS1_RX") (class "Default")
      (node (ref "J6") (pin "5") (pinfunction "5_5") (pintype "passive"))
      (node (ref "U9") (pin "5") (pinfunction "RXD_5") (pintype "passive"))
    )
    (net (code "39") (name "RCB_GPS1_TP1") (class "Default")
      (node (ref "J6") (pin "6") (pinfunction "6_6") (pintype "passive"))
      (node (ref "U9") (pin "6") (pinfunction "TP1_6") (pintype "passive"))
    )
    (net (code "40") (name "RCB_GPS1_TP2") (class "Default")
      (node (ref "J6") (pin "7") (pinfunction "7_7") (pintype "passive"))
      (node (ref "U9") (pin "7") (pinfunction "TP2_7") (pintype "passive"))
    )
    (net (code "41") (name "RCB_GPS1_TX") (class "Default")
      (node (ref "J6") (pin "3") (pinfunction "3_3") (pintype "passive"))
      (node (ref "U9") (pin "3") (pinfunction "TXD_3") (pintype "passive"))
    )
    (net (code "42") (name "RCB_GPS2_PIN11") (class "Default")
      (node (ref "J13") (pin "11") (pinfunction "11_11") (pintype "passive"))
    )
    (net (code "43") (name "RCB_GPS2_PIN12") (class "Default")
      (node (ref "J13") (pin "12") (pinfunction "12_12") (pintype "passive"))
    )
    (net (code "44") (name "RCB_GPS2_RX") (class "Default")
      (node (ref "J13") (pin "5") (pinfunction "5_5") (pintype "passive"))
      (node (ref "U15") (pin "5") (pinfunction "RXD_5") (pintype "passive"))
    )
    (net (code "45") (name "RCB_GPS2_TP1") (class "Default")
      (node (ref "J13") (pin "6") (pinfunction "6_6") (pintype "passive"))
      (node (ref "U15") (pin "6") (pinfunction "TP1_6") (pintype "passive"))
    )
    (net (code "46") (name "RCB_GPS2_TP2") (class "Default")
      (node (ref "J13") (pin "7") (pinfunction "7_7") (pintype "passive"))
      (node (ref "U15") (pin "7") (pinfunction "TP2_7") (pintype "passive"))
    )
    (net (code "47") (name "RCB_GPS2_TX") (class "Default")
      (node (ref "J13") (pin "3") (pinfunction "3_3") (pintype "passive"))
      (node (ref "U15") (pin "3") (pinfunction "TXD_3") (pintype "passive"))
    )
    (net (code "48") (name "SCL") (class "Default")
      (node (ref "U7") (pin "1") (pinfunction "SCL_1") (pintype "input"))
    )
    (net (code "49") (name "SDA") (class "Default")
      (node (ref "U7") (pin "3") (pinfunction "SDA_3") (pintype "bidirectional"))
    )
    (net (code "50") (name "SENS1_I2C_SCL") (class "Default")
      (node (ref "U13") (pin "19") (pinfunction "COM1_19") (pintype "bidirectional"))
      (node (ref "U14") (pin "4") (pinfunction "SCK_4") (pintype "input"))
    )
    (net (code "51") (name "SENS1_I2C_SDA") (class "Default")
      (node (ref "U13") (pin "20") (pinfunction "COM0_20") (pintype "bidirectional"))
      (node (ref "U14") (pin "3") (pinfunction "SDI_3") (pintype "bidirectional"))
    )
    (net (code "52") (name "unconnected-(U13-NC-Pad1)") (class "Default")
      (node (ref "U13") (pin "1") (pinfunction "NC_1") (pintype "passive"))
    )
    (net (code "53") (name "unconnected-(U13-NC-Pad12)") (class "Default")
      (node (ref "U13") (pin "12") (pinfunction "NC_12") (pintype "passive"))
    )
    (net (code "54") (name "unconnected-(U13-NC-Pad13)") (class "Default")
      (node (ref "U13") (pin "13") (pinfunction "NC_13") (pintype "passive"))
    )
    (net (code "55") (name "unconnected-(U13-NC-Pad15)") (class "Default")
      (node (ref "U13") (pin "15") (pinfunction "NC_15") (pintype "passive"))
    )
    (net (code "56") (name "unconnected-(U13-NC-Pad16)") (class "Default")
      (node (ref "U13") (pin "16") (pinfunction "NC_16") (pintype "passive"))
    )
    (net (code "57") (name "unconnected-(U13-NC-Pad21)") (class "Default")
      (node (ref "U13") (pin "21") (pinfunction "NC_21") (pintype "passive"))
    )
    (net (code "58") (name "unconnected-(U13-NC-Pad22)") (class "Default")
      (node (ref "U13") (pin "22") (pinfunction "NC_22") (pintype "passive"))
    )
    (net (code "59") (name "unconnected-(U13-NC-Pad23)") (class "Default")
      (node (ref "U13") (pin "23") (pinfunction "NC_23") (pintype "passive"))
    )
    (net (code "60") (name "unconnected-(U13-NC-Pad24)") (class "Default")
      (node (ref "U13") (pin "24") (pinfunction "NC_24") (pintype "passive"))
    )
    (net (code "61") (name "unconnected-(U25-NC-Pad5)") (class "Default")
      (node (ref "U25") (pin "5") (pinfunction "NC_5") (pintype "passive"))
    )
  )
)
